# schema_v4_2.net
KiCad netlist of a schematic drawn in EAGLE
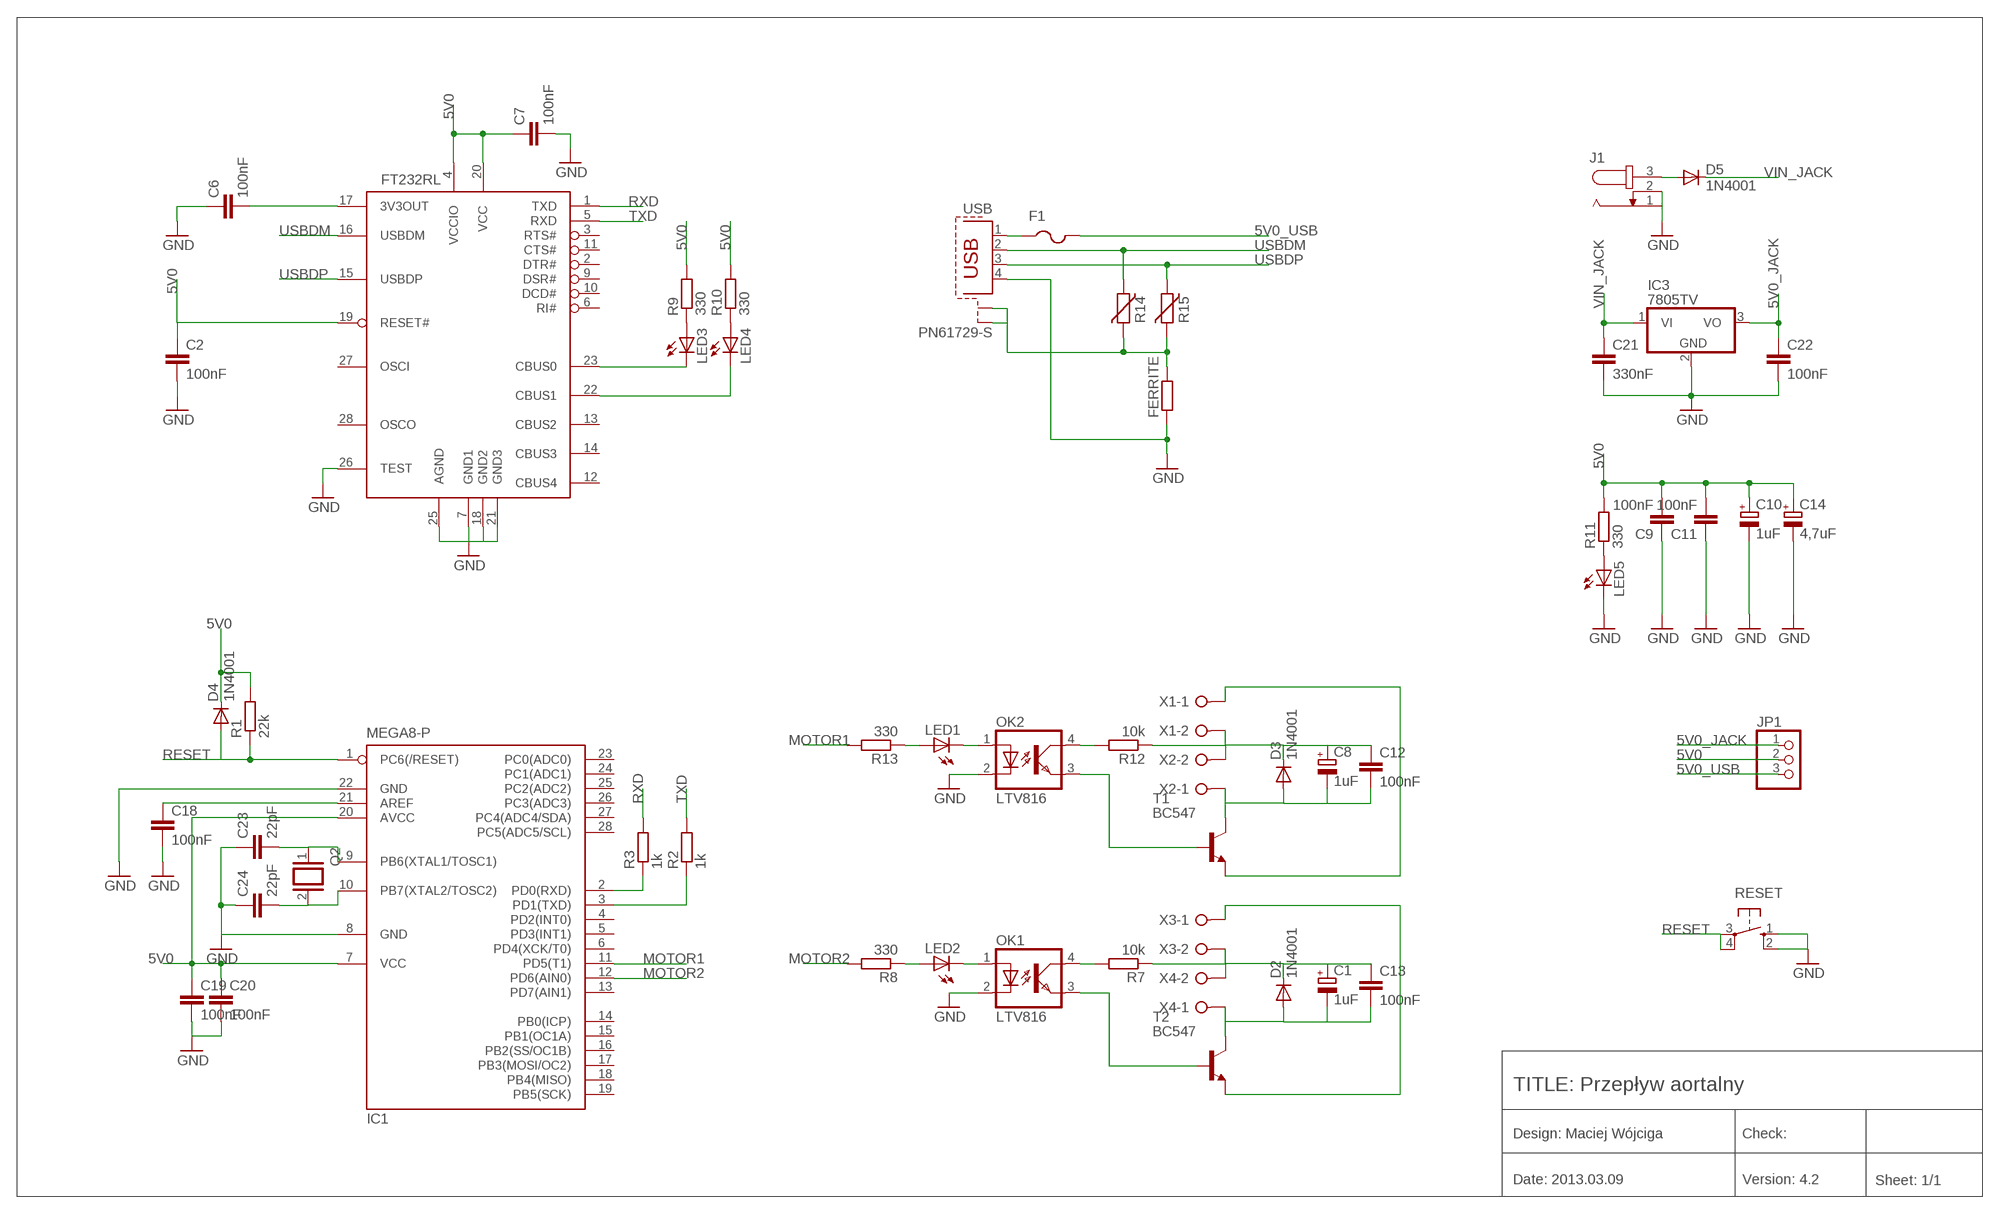
[diagram p0: schematic, sheet 1]

(export (version "E")
  (design (tool "Eeschema 10.0.6"))
  (components
    (comp (ref "C1")
      (value "1uF")
      (footprint "eagle-import:E2,5-5")
      (libsource (lib "eagle-import") (part "CPOL-EUE2.5-5"))
    )
    (comp (ref "C2")
      (value "100nF")
      (footprint "eagle-import:C0603K")
      (libsource (lib "eagle-import") (part "C-EUC0603K"))
    )
    (comp (ref "C6")
      (value "100nF")
      (footprint "eagle-import:C0603K")
      (libsource (lib "eagle-import") (part "C-EUC0603K"))
    )
    (comp (ref "C7")
      (value "100nF")
      (footprint "eagle-import:C0603K")
      (libsource (lib "eagle-import") (part "C-EUC0603K"))
    )
    (comp (ref "C8")
      (value "1uF")
      (footprint "eagle-import:E2,5-5")
      (libsource (lib "eagle-import") (part "CPOL-EUE2.5-5"))
    )
    (comp (ref "C9")
      (value "100nF")
      (footprint "eagle-import:C025-025X050")
      (libsource (lib "eagle-import") (part "C-EU025-025X050"))
    )
    (comp (ref "C10")
      (value "1uF")
      (footprint "eagle-import:E2,5-5")
      (libsource (lib "eagle-import") (part "CPOL-EUE2.5-5"))
    )
    (comp (ref "C11")
      (value "100nF")
      (footprint "eagle-import:C025-025X050")
      (libsource (lib "eagle-import") (part "C-EU025-025X050"))
    )
    (comp (ref "C12")
      (value "100nF")
      (footprint "eagle-import:C025-025X050")
      (libsource (lib "eagle-import") (part "C-EU025-025X050"))
    )
    (comp (ref "C13")
      (value "100nF")
      (footprint "eagle-import:C025-025X050")
      (libsource (lib "eagle-import") (part "C-EU025-025X050"))
    )
    (comp (ref "C14")
      (value "4,7uF")
      (footprint "eagle-import:E2,5-5")
      (libsource (lib "eagle-import") (part "CPOL-EUE2.5-5"))
    )
    (comp (ref "C18")
      (value "100nF")
      (footprint "eagle-import:C0805")
      (libsource (lib "eagle-import") (part "C-EUC0805"))
    )
    (comp (ref "C19")
      (value "100nF")
      (footprint "eagle-import:C025-025X050")
      (libsource (lib "eagle-import") (part "C-EU025-025X050"))
    )
    (comp (ref "C20")
      (value "100nF")
      (footprint "eagle-import:C025-025X050")
      (libsource (lib "eagle-import") (part "C-EU025-025X050"))
    )
    (comp (ref "C21")
      (value "330nF")
      (footprint "eagle-import:C025-025X050")
      (libsource (lib "eagle-import") (part "C-EU025-025X050"))
    )
    (comp (ref "C22")
      (value "100nF")
      (footprint "eagle-import:C025-025X050")
      (libsource (lib "eagle-import") (part "C-EU025-025X050"))
    )
    (comp (ref "C23")
      (value "22pF")
      (footprint "eagle-import:C025-025X050")
      (libsource (lib "eagle-import") (part "C-EU025-025X050"))
    )
    (comp (ref "C24")
      (value "22pF")
      (footprint "eagle-import:C025-025X050")
      (libsource (lib "eagle-import") (part "C-EU025-025X050"))
    )
    (comp (ref "D2")
      (value "1N4001")
      (footprint "eagle-import:DO41-10")
      (libsource (lib "eagle-import") (part "1N4004"))
    )
    (comp (ref "D3")
      (value "1N4001")
      (footprint "eagle-import:DO41-10")
      (libsource (lib "eagle-import") (part "1N4004"))
    )
    (comp (ref "D4")
      (value "1N4001")
      (footprint "eagle-import:DO41-10")
      (libsource (lib "eagle-import") (part "1N4004"))
    )
    (comp (ref "D5")
      (value "1N4001")
      (footprint "eagle-import:DO41-10")
      (libsource (lib "eagle-import") (part "1N4004"))
    )
    (comp (ref "F1")
      (value "PTCFUSE-1812")
      (footprint "eagle-import:1812")
      (libsource (lib "eagle-import") (part "PTCFUSE-1812"))
    )
    (comp (ref "FERRITE")
      (value "R-EU_M0805")
      (footprint "eagle-import:M0805")
      (libsource (lib "eagle-import") (part "resistor_R-EU_M0805"))
    )
    (comp (ref "FT232RL")
      (value "FT232RL")
      (footprint "eagle-import:SSOP28DB")
      (libsource (lib "eagle-import") (part "FT232RL"))
    )
    (comp (ref "IC1")
      (value "MEGA8-P")
      (footprint "eagle-import:DIL28-3")
      (libsource (lib "eagle-import") (part "MEGA8-P"))
    )
    (comp (ref "IC3")
      (value "7805TV")
      (footprint "eagle-import:TO220V")
      (libsource (lib "eagle-import") (part "78TV05"))
    )
    (comp (ref "J1")
      (value "JACK-PLUG0")
      (footprint "eagle-import:SPC4077")
      (libsource (lib "eagle-import") (part "JACK-PLUG0"))
    )
    (comp (ref "JP1")
      (value "PINHD-1X3")
      (footprint "eagle-import:1X03")
      (libsource (lib "eagle-import") (part "PINHD-1X3"))
    )
    (comp (ref "LED1")
      (value "LED3MM")
      (footprint "eagle-import:LED3MM")
      (libsource (lib "eagle-import") (part "LED3MM"))
    )
    (comp (ref "LED2")
      (value "LED3MM")
      (footprint "eagle-import:LED3MM")
      (libsource (lib "eagle-import") (part "LED3MM"))
    )
    (comp (ref "LED3")
      (value "LED3MM")
      (footprint "eagle-import:LED3MM")
      (libsource (lib "eagle-import") (part "LED3MM"))
    )
    (comp (ref "LED4")
      (value "LED3MM")
      (footprint "eagle-import:LED3MM")
      (libsource (lib "eagle-import") (part "LED3MM"))
    )
    (comp (ref "LED5")
      (value "LED3MM")
      (footprint "eagle-import:LED3MM")
      (libsource (lib "eagle-import") (part "LED3MM"))
    )
    (comp (ref "OK1")
      (value "LTV816")
      (footprint "eagle-import:DIL04")
      (libsource (lib "eagle-import") (part "LTV816"))
    )
    (comp (ref "OK2")
      (value "LTV816")
      (footprint "eagle-import:DIL04")
      (libsource (lib "eagle-import") (part "LTV816"))
    )
    (comp (ref "Q2")
      (value "XTAL/S")
      (footprint "eagle-import:QS")
      (libsource (lib "eagle-import") (part "XTAL/S"))
    )
    (comp (ref "R1")
      (value "22k")
      (footprint "eagle-import:0207_10")
      (libsource (lib "eagle-import") (part "R-EU_0207/10"))
    )
    (comp (ref "R2")
      (value "1k")
      (footprint "eagle-import:0207_10")
      (libsource (lib "eagle-import") (part "R-EU_0207/10"))
    )
    (comp (ref "R3")
      (value "1k")
      (footprint "eagle-import:0207_10")
      (libsource (lib "eagle-import") (part "R-EU_0207/10"))
    )
    (comp (ref "R7")
      (value "10k")
      (footprint "eagle-import:0207_10")
      (libsource (lib "eagle-import") (part "R-EU_0207/10"))
    )
    (comp (ref "R8")
      (value "330")
      (footprint "eagle-import:0207_10")
      (libsource (lib "eagle-import") (part "R-EU_0207/10"))
    )
    (comp (ref "R9")
      (value "330")
      (footprint "eagle-import:0207_10")
      (libsource (lib "eagle-import") (part "R-EU_0207/10"))
    )
    (comp (ref "R10")
      (value "330")
      (footprint "eagle-import:0207_10")
      (libsource (lib "eagle-import") (part "R-EU_0207/10"))
    )
    (comp (ref "R11")
      (value "330")
      (footprint "eagle-import:0207_10")
      (libsource (lib "eagle-import") (part "R-EU_0207/10"))
    )
    (comp (ref "R12")
      (value "10k")
      (footprint "eagle-import:0207_10")
      (libsource (lib "eagle-import") (part "R-EU_0207/10"))
    )
    (comp (ref "R13")
      (value "330")
      (footprint "eagle-import:0207_10")
      (libsource (lib "eagle-import") (part "R-EU_0207/10"))
    )
    (comp (ref "R14")
      (value "VARISTORCN0603")
      (footprint "eagle-import:CT_CN0603")
      (libsource (lib "eagle-import") (part "VARISTORCN0603"))
    )
    (comp (ref "R15")
      (value "VARISTORCN0603")
      (footprint "eagle-import:CT_CN0603")
      (libsource (lib "eagle-import") (part "VARISTORCN0603"))
    )
    (comp (ref "RESET")
      (value "10-XX")
      (footprint "eagle-import:B3F-10XX")
      (fields (field (name "MPN") "B3F-1000"))
      (libsource (lib "eagle-import") (part "10-XX"))
    )
    (comp (ref "T1")
      (value "BC547")
      (footprint "eagle-import:TO92")
      (libsource (lib "eagle-import") (part "BC547"))
    )
    (comp (ref "T2")
      (value "BC547")
      (footprint "eagle-import:TO92")
      (libsource (lib "eagle-import") (part "BC547"))
    )
    (comp (ref "USB")
      (value "PN61729-S")
      (footprint "eagle-import:PN61729-S")
      (fields (field (name "OC_FARNELL") "unknown") (field (name "OC_NEWARK") "unknown"))
      (libsource (lib "eagle-import") (part "PN61729-S"))
    )
    (comp (ref "X1")
      (value "W237-02P")
      (footprint "eagle-import:W237-132")
      (fields (field (name "OC_FARNELL") "unknown") (field (name "OC_NEWARK") "unknown"))
      (libsource (lib "eagle-import") (part "W237-02P"))
    )
    (comp (ref "X2")
      (value "W237-02P")
      (footprint "eagle-import:W237-132")
      (fields (field (name "OC_FARNELL") "unknown") (field (name "OC_NEWARK") "unknown"))
      (libsource (lib "eagle-import") (part "W237-02P"))
    )
    (comp (ref "X3")
      (value "W237-02P")
      (footprint "eagle-import:W237-132")
      (fields (field (name "OC_FARNELL") "unknown") (field (name "OC_NEWARK") "unknown"))
      (libsource (lib "eagle-import") (part "W237-02P"))
    )
    (comp (ref "X4")
      (value "W237-02P")
      (footprint "eagle-import:W237-132")
      (fields (field (name "OC_FARNELL") "unknown") (field (name "OC_NEWARK") "unknown"))
      (libsource (lib "eagle-import") (part "W237-02P"))
    )
  )
  (nets
    (net (code "1") (name "/5V0") (class "Default")
      (node (ref "C10") (pin "+") (pinfunction "+_+") (pintype "passive"))
      (node (ref "C11") (pin "2") (pinfunction "2_2") (pintype "passive"))
      (node (ref "C14") (pin "+") (pinfunction "+_+") (pintype "passive"))
      (node (ref "C19") (pin "1") (pinfunction "1_1") (pintype "passive"))
      (node (ref "C2") (pin "1") (pinfunction "1_1") (pintype "passive"))
      (node (ref "C20") (pin "1") (pinfunction "1_1") (pintype "passive"))
      (node (ref "C7") (pin "1") (pinfunction "1_1") (pintype "passive"))
      (node (ref "C9") (pin "2") (pinfunction "2_2") (pintype "passive"))
      (node (ref "D4") (pin "C") (pinfunction "C_C") (pintype "passive"))
      (node (ref "FT232RL") (pin "19") (pinfunction "RESET#_19") (pintype "input"))
      (node (ref "FT232RL") (pin "20") (pinfunction "VCC_20") (pintype "power_in"))
      (node (ref "FT232RL") (pin "4") (pinfunction "VCCIO_4") (pintype "power_in"))
      (node (ref "IC1") (pin "20") (pinfunction "AVCC_20") (pintype "power_in"))
      (node (ref "IC1") (pin "7") (pinfunction "VCC_7") (pintype "power_in"))
      (node (ref "JP1") (pin "2") (pinfunction "2_2") (pintype "passive"))
      (node (ref "R1") (pin "2") (pinfunction "2_2") (pintype "passive"))
      (node (ref "R10") (pin "2") (pinfunction "2_2") (pintype "passive"))
      (node (ref "R11") (pin "2") (pinfunction "2_2") (pintype "passive"))
      (node (ref "R9") (pin "2") (pinfunction "2_2") (pintype "passive"))
    )
    (net (code "2") (name "/5V0_JACK") (class "Default")
      (node (ref "C22") (pin "1") (pinfunction "1_1") (pintype "passive"))
      (node (ref "IC3") (pin "3") (pinfunction "VO_3") (pintype "passive"))
      (node (ref "JP1") (pin "1") (pinfunction "1_1") (pintype "passive"))
    )
    (net (code "3") (name "/5V0_USB") (class "Default")
      (node (ref "F1") (pin "2") (pinfunction "2_2") (pintype "passive"))
      (node (ref "JP1") (pin "3") (pinfunction "3_3") (pintype "passive"))
    )
    (net (code "4") (name "/MOTOR1") (class "Default")
      (node (ref "IC1") (pin "11") (pinfunction "PD5(T1)_11") (pintype "bidirectional"))
      (node (ref "R13") (pin "2") (pinfunction "2_2") (pintype "passive"))
    )
    (net (code "5") (name "/MOTOR2") (class "Default")
      (node (ref "IC1") (pin "12") (pinfunction "PD6(AIN0)_12") (pintype "bidirectional"))
      (node (ref "R8") (pin "2") (pinfunction "2_2") (pintype "passive"))
    )
    (net (code "6") (name "/RESET") (class "Default")
      (node (ref "D4") (pin "A") (pinfunction "A_A") (pintype "passive"))
      (node (ref "IC1") (pin "1") (pinfunction "PC6(/RESET)_1") (pintype "bidirectional"))
      (node (ref "R1") (pin "1") (pinfunction "1_1") (pintype "passive"))
      (node (ref "RESET") (pin "3") (pinfunction "P_3") (pintype "passive"))
      (node (ref "RESET") (pin "4") (pinfunction "P1_4") (pintype "passive"))
    )
    (net (code "7") (name "/RXD") (class "Default")
      (node (ref "FT232RL") (pin "1") (pinfunction "TXD_1") (pintype "output"))
      (node (ref "R3") (pin "2") (pinfunction "2_2") (pintype "passive"))
    )
    (net (code "8") (name "/TXD") (class "Default")
      (node (ref "FT232RL") (pin "5") (pinfunction "RXD_5") (pintype "input"))
      (node (ref "R2") (pin "2") (pinfunction "2_2") (pintype "passive"))
    )
    (net (code "9") (name "/USBDM") (class "Default")
      (node (ref "FT232RL") (pin "16") (pinfunction "USBDM_16") (pintype "bidirectional"))
      (node (ref "R14") (pin "1") (pinfunction "1_1") (pintype "passive"))
      (node (ref "USB") (pin "2") (pinfunction "2_2") (pintype "passive"))
    )
    (net (code "10") (name "/USBDP") (class "Default")
      (node (ref "FT232RL") (pin "15") (pinfunction "USBDP_15") (pintype "bidirectional"))
      (node (ref "R15") (pin "1") (pinfunction "1_1") (pintype "passive"))
      (node (ref "USB") (pin "3") (pinfunction "3_3") (pintype "passive"))
    )
    (net (code "11") (name "/VIN_JACK") (class "Default")
      (node (ref "C21") (pin "1") (pinfunction "1_1") (pintype "passive"))
      (node (ref "D5") (pin "C") (pinfunction "C_C") (pintype "passive"))
      (node (ref "IC3") (pin "1") (pinfunction "VI_1") (pintype "input"))
    )
    (net (code "12") (name "GND") (class "Default")
      (node (ref "C10") (pin "-") (pinfunction "-_-") (pintype "passive"))
      (node (ref "C11") (pin "1") (pinfunction "1_1") (pintype "passive"))
      (node (ref "C14") (pin "-") (pinfunction "-_-") (pintype "passive"))
      (node (ref "C18") (pin "2") (pinfunction "2_2") (pintype "passive"))
      (node (ref "C19") (pin "2") (pinfunction "2_2") (pintype "passive"))
      (node (ref "C2") (pin "2") (pinfunction "2_2") (pintype "passive"))
      (node (ref "C20") (pin "2") (pinfunction "2_2") (pintype "passive"))
      (node (ref "C21") (pin "2") (pinfunction "2_2") (pintype "passive"))
      (node (ref "C22") (pin "2") (pinfunction "2_2") (pintype "passive"))
      (node (ref "C23") (pin "1") (pinfunction "1_1") (pintype "passive"))
      (node (ref "C24") (pin "1") (pinfunction "1_1") (pintype "passive"))
      (node (ref "C6") (pin "1") (pinfunction "1_1") (pintype "passive"))
      (node (ref "C7") (pin "2") (pinfunction "2_2") (pintype "passive"))
      (node (ref "C9") (pin "1") (pinfunction "1_1") (pintype "passive"))
      (node (ref "FERRITE") (pin "1") (pinfunction "1_1") (pintype "passive"))
      (node (ref "FT232RL") (pin "18") (pinfunction "GND2_18") (pintype "power_in"))
      (node (ref "FT232RL") (pin "21") (pinfunction "GND3_21") (pintype "power_in"))
      (node (ref "FT232RL") (pin "25") (pinfunction "AGND_25") (pintype "power_in"))
      (node (ref "FT232RL") (pin "26") (pinfunction "TEST_26") (pintype "input"))
      (node (ref "FT232RL") (pin "7") (pinfunction "GND1_7") (pintype "power_in"))
      (node (ref "IC1") (pin "22") (pinfunction "GND_22") (pintype "power_in"))
      (node (ref "IC1") (pin "8") (pinfunction "GND_8") (pintype "power_in"))
      (node (ref "IC3") (pin "2") (pinfunction "GND_2") (pintype "passive"))
      (node (ref "J1") (pin "1") (pinfunction "1_1") (pintype "passive"))
      (node (ref "J1") (pin "2") (pinfunction "2_2") (pintype "passive"))
      (node (ref "LED5") (pin "K") (pinfunction "C_K") (pintype "passive"))
      (node (ref "OK1") (pin "2") (pinfunction "C_2") (pintype "passive"))
      (node (ref "OK2") (pin "2") (pinfunction "C_2") (pintype "passive"))
      (node (ref "RESET") (pin "1") (pinfunction "S_1") (pintype "passive"))
      (node (ref "RESET") (pin "2") (pinfunction "S1_2") (pintype "passive"))
      (node (ref "USB") (pin "4") (pinfunction "4_4") (pintype "passive"))
    )
    (net (code "13") (name "Net-(D5-PadA)") (class "Default")
      (node (ref "D5") (pin "A") (pinfunction "A_A") (pintype "passive"))
      (node (ref "J1") (pin "3") (pinfunction "3_3") (pintype "passive"))
    )
    (net (code "14") (name "Net-(F1-Pad1)") (class "Default")
      (node (ref "F1") (pin "1") (pinfunction "1_1") (pintype "passive"))
      (node (ref "USB") (pin "1") (pinfunction "1_1") (pintype "passive"))
    )
    (net (code "15") (name "Net-(FERRITE-Pad2)") (class "Default")
      (node (ref "FERRITE") (pin "2") (pinfunction "2_2") (pintype "passive"))
      (node (ref "R14") (pin "2") (pinfunction "2_2") (pintype "passive"))
      (node (ref "R15") (pin "2") (pinfunction "2_2") (pintype "passive"))
      (node (ref "USB") (pin "S1") (pinfunction "S1_S1") (pintype "passive"))
      (node (ref "USB") (pin "S2") (pinfunction "S2_S2") (pintype "passive"))
    )
    (net (code "16") (name "Net-(FT232RL-3V3OUT)") (class "Default")
      (node (ref "C6") (pin "2") (pinfunction "2_2") (pintype "passive"))
      (node (ref "FT232RL") (pin "17") (pinfunction "3V3OUT_17") (pintype "output"))
    )
    (net (code "17") (name "Net-(FT232RL-CBUS0)") (class "Default")
      (node (ref "FT232RL") (pin "23") (pinfunction "CBUS0_23") (pintype "bidirectional"))
      (node (ref "LED3") (pin "K") (pinfunction "C_K") (pintype "passive"))
    )
    (net (code "18") (name "Net-(FT232RL-CBUS1)") (class "Default")
      (node (ref "FT232RL") (pin "22") (pinfunction "CBUS1_22") (pintype "bidirectional"))
      (node (ref "LED4") (pin "K") (pinfunction "C_K") (pintype "passive"))
    )
    (net (code "19") (name "Net-(IC1-AREF)") (class "Default")
      (node (ref "C18") (pin "1") (pinfunction "1_1") (pintype "passive"))
      (node (ref "IC1") (pin "21") (pinfunction "AREF_21") (pintype "passive"))
    )
    (net (code "20") (name "Net-(IC1-PB6(XTAL1{slash}TOSC1))") (class "Default")
      (node (ref "C23") (pin "2") (pinfunction "2_2") (pintype "passive"))
      (node (ref "IC1") (pin "9") (pinfunction "PB6(XTAL1/TOSC1)_9") (pintype "bidirectional"))
      (node (ref "Q2") (pin "1") (pinfunction "1_1") (pintype "passive"))
    )
    (net (code "21") (name "Net-(IC1-PB7(XTAL2{slash}TOSC2))") (class "Default")
      (node (ref "C24") (pin "2") (pinfunction "2_2") (pintype "passive"))
      (node (ref "IC1") (pin "10") (pinfunction "PB7(XTAL2/TOSC2)_10") (pintype "bidirectional"))
      (node (ref "Q2") (pin "2") (pinfunction "2_2") (pintype "passive"))
    )
    (net (code "22") (name "Net-(IC1-PD0(RXD))") (class "Default")
      (node (ref "IC1") (pin "2") (pinfunction "PD0(RXD)_2") (pintype "bidirectional"))
      (node (ref "R3") (pin "1") (pinfunction "1_1") (pintype "passive"))
    )
    (net (code "23") (name "Net-(IC1-PD1(TXD))") (class "Default")
      (node (ref "IC1") (pin "3") (pinfunction "PD1(TXD)_3") (pintype "bidirectional"))
      (node (ref "R2") (pin "1") (pinfunction "1_1") (pintype "passive"))
    )
    (net (code "24") (name "Net-(LED1-C)") (class "Default")
      (node (ref "LED1") (pin "K") (pinfunction "C_K") (pintype "passive"))
      (node (ref "OK2") (pin "1") (pinfunction "A_1") (pintype "passive"))
    )
    (net (code "25") (name "Net-(LED1-PadA)") (class "Default")
      (node (ref "LED1") (pin "A") (pinfunction "A_A") (pintype "passive"))
      (node (ref "R13") (pin "1") (pinfunction "1_1") (pintype "passive"))
    )
    (net (code "26") (name "Net-(LED2-C)") (class "Default")
      (node (ref "LED2") (pin "K") (pinfunction "C_K") (pintype "passive"))
      (node (ref "OK1") (pin "1") (pinfunction "A_1") (pintype "passive"))
    )
    (net (code "27") (name "Net-(LED2-PadA)") (class "Default")
      (node (ref "LED2") (pin "A") (pinfunction "A_A") (pintype "passive"))
      (node (ref "R8") (pin "1") (pinfunction "1_1") (pintype "passive"))
    )
    (net (code "28") (name "Net-(LED3-PadA)") (class "Default")
      (node (ref "LED3") (pin "A") (pinfunction "A_A") (pintype "passive"))
      (node (ref "R9") (pin "1") (pinfunction "1_1") (pintype "passive"))
    )
    (net (code "29") (name "Net-(LED4-PadA)") (class "Default")
      (node (ref "LED4") (pin "A") (pinfunction "A_A") (pintype "passive"))
      (node (ref "R10") (pin "1") (pinfunction "1_1") (pintype "passive"))
    )
    (net (code "30") (name "Net-(LED5-PadA)") (class "Default")
      (node (ref "LED5") (pin "A") (pinfunction "A_A") (pintype "passive"))
      (node (ref "R11") (pin "1") (pinfunction "1_1") (pintype "passive"))
    )
    (net (code "31") (name "Net-(OK1-COL)") (class "Default")
      (node (ref "OK1") (pin "4") (pinfunction "COL_4") (pintype "passive"))
      (node (ref "R7") (pin "2") (pinfunction "2_2") (pintype "passive"))
    )
    (net (code "32") (name "Net-(OK1-EMIT)") (class "Default")
      (node (ref "OK1") (pin "3") (pinfunction "EMIT_3") (pintype "passive"))
      (node (ref "T2") (pin "2") (pinfunction "B_2") (pintype "passive"))
    )
    (net (code "33") (name "Net-(OK2-COL)") (class "Default")
      (node (ref "OK2") (pin "4") (pinfunction "COL_4") (pintype "passive"))
      (node (ref "R12") (pin "2") (pinfunction "2_2") (pintype "passive"))
    )
    (net (code "34") (name "Net-(OK2-EMIT)") (class "Default")
      (node (ref "OK2") (pin "3") (pinfunction "EMIT_3") (pintype "passive"))
      (node (ref "T1") (pin "2") (pinfunction "B_2") (pintype "passive"))
    )
    (net (code "35") (name "Net-(T1-C)") (class "Default")
      (node (ref "C12") (pin "2") (pinfunction "2_2") (pintype "passive"))
      (node (ref "C8") (pin "-") (pinfunction "-_-") (pintype "passive"))
      (node (ref "D3") (pin "A") (pinfunction "A_A") (pintype "passive"))
      (node (ref "T1") (pin "3") (pinfunction "C_3") (pintype "passive"))
      (node (ref "X2") (pin "1") (pinfunction "KL_1") (pintype "passive"))
    )
    (net (code "36") (name "Net-(T1-E)") (class "Default")
      (node (ref "T1") (pin "1") (pinfunction "E_1") (pintype "passive"))
      (node (ref "X1") (pin "1") (pinfunction "KL_1") (pintype "passive"))
    )
    (net (code "37") (name "Net-(T2-C)") (class "Default")
      (node (ref "C1") (pin "-") (pinfunction "-_-") (pintype "passive"))
      (node (ref "C13") (pin "2") (pinfunction "2_2") (pintype "passive"))
      (node (ref "D2") (pin "A") (pinfunction "A_A") (pintype "passive"))
      (node (ref "T2") (pin "3") (pinfunction "C_3") (pintype "passive"))
      (node (ref "X4") (pin "1") (pinfunction "KL_1") (pintype "passive"))
    )
    (net (code "38") (name "Net-(T2-E)") (class "Default")
      (node (ref "T2") (pin "1") (pinfunction "E_1") (pintype "passive"))
      (node (ref "X3") (pin "1") (pinfunction "KL_1") (pintype "passive"))
    )
    (net (code "39") (name "Net-(X1B-KL)") (class "Default")
      (node (ref "C12") (pin "1") (pinfunction "1_1") (pintype "passive"))
      (node (ref "C8") (pin "+") (pinfunction "+_+") (pintype "passive"))
      (node (ref "D3") (pin "C") (pinfunction "C_C") (pintype "passive"))
      (node (ref "R12") (pin "1") (pinfunction "1_1") (pintype "passive"))
      (node (ref "X1") (pin "2") (pinfunction "KL_2") (pintype "passive"))
      (node (ref "X2") (pin "2") (pinfunction "KL_2") (pintype "passive"))
    )
    (net (code "40") (name "Net-(X3B-KL)") (class "Default")
      (node (ref "C1") (pin "+") (pinfunction "+_+") (pintype "passive"))
      (node (ref "C13") (pin "1") (pinfunction "1_1") (pintype "passive"))
      (node (ref "D2") (pin "C") (pinfunction "C_C") (pintype "passive"))
      (node (ref "R7") (pin "1") (pinfunction "1_1") (pintype "passive"))
      (node (ref "X3") (pin "2") (pinfunction "KL_2") (pintype "passive"))
      (node (ref "X4") (pin "2") (pinfunction "KL_2") (pintype "passive"))
    )
    (net (code "41") (name "unconnected-(FT232RL-CBUS2-Pad13)") (class "Default")
      (node (ref "FT232RL") (pin "13") (pinfunction "CBUS2_13") (pintype "bidirectional"))
    )
    (net (code "42") (name "unconnected-(FT232RL-CBUS3-Pad14)") (class "Default")
      (node (ref "FT232RL") (pin "14") (pinfunction "CBUS3_14") (pintype "bidirectional"))
    )
    (net (code "43") (name "unconnected-(FT232RL-CBUS4-Pad12)") (class "Default")
      (node (ref "FT232RL") (pin "12") (pinfunction "CBUS4_12") (pintype "bidirectional"))
    )
    (net (code "44") (name "unconnected-(FT232RL-CTS#-Pad11)") (class "Default")
      (node (ref "FT232RL") (pin "11") (pinfunction "CTS#_11") (pintype "input"))
    )
    (net (code "45") (name "unconnected-(FT232RL-DCD#-Pad10)") (class "Default")
      (node (ref "FT232RL") (pin "10") (pinfunction "DCD#_10") (pintype "input"))
    )
    (net (code "46") (name "unconnected-(FT232RL-DSR#-Pad9)") (class "Default")
      (node (ref "FT232RL") (pin "9") (pinfunction "DSR#_9") (pintype "input"))
    )
    (net (code "47") (name "unconnected-(FT232RL-DTR#-Pad2)") (class "Default")
      (node (ref "FT232RL") (pin "2") (pinfunction "DTR#_2") (pintype "output"))
    )
    (net (code "48") (name "unconnected-(FT232RL-OSCI-Pad27)") (class "Default")
      (node (ref "FT232RL") (pin "27") (pinfunction "OSCI_27") (pintype "input"))
    )
    (net (code "49") (name "unconnected-(FT232RL-OSCO-Pad28)") (class "Default")
      (node (ref "FT232RL") (pin "28") (pinfunction "OSCO_28") (pintype "output"))
    )
    (net (code "50") (name "unconnected-(FT232RL-RI#-Pad6)") (class "Default")
      (node (ref "FT232RL") (pin "6") (pinfunction "RI#_6") (pintype "input"))
    )
    (net (code "51") (name "unconnected-(FT232RL-RTS#-Pad3)") (class "Default")
      (node (ref "FT232RL") (pin "3") (pinfunction "RTS#_3") (pintype "output"))
    )
    (net (code "52") (name "unconnected-(IC1-PB0(ICP)-Pad14)") (class "Default")
      (node (ref "IC1") (pin "14") (pinfunction "PB0(ICP)_14") (pintype "bidirectional"))
    )
    (net (code "53") (name "unconnected-(IC1-PB1(OC1A)-Pad15)") (class "Default")
      (node (ref "IC1") (pin "15") (pinfunction "PB1(OC1A)_15") (pintype "bidirectional"))
    )
    (net (code "54") (name "unconnected-(IC1-PB2(SS{slash}OC1B)-Pad16)") (class "Default")
      (node (ref "IC1") (pin "16") (pinfunction "PB2(SS/OC1B)_16") (pintype "bidirectional"))
    )
    (net (code "55") (name "unconnected-(IC1-PB3(MOSI{slash}OC2)-Pad17)") (class "Default")
      (node (ref "IC1") (pin "17") (pinfunction "PB3(MOSI/OC2)_17") (pintype "bidirectional"))
    )
    (net (code "56") (name "unconnected-(IC1-PB4(MISO)-Pad18)") (class "Default")
      (node (ref "IC1") (pin "18") (pinfunction "PB4(MISO)_18") (pintype "bidirectional"))
    )
    (net (code "57") (name "unconnected-(IC1-PB5(SCK)-Pad19)") (class "Default")
      (node (ref "IC1") (pin "19") (pinfunction "PB5(SCK)_19") (pintype "bidirectional"))
    )
    (net (code "58") (name "unconnected-(IC1-PC0(ADC0)-Pad23)") (class "Default")
      (node (ref "IC1") (pin "23") (pinfunction "PC0(ADC0)_23") (pintype "bidirectional"))
    )
    (net (code "59") (name "unconnected-(IC1-PC1(ADC1)-Pad24)") (class "Default")
      (node (ref "IC1") (pin "24") (pinfunction "PC1(ADC1)_24") (pintype "bidirectional"))
    )
    (net (code "60") (name "unconnected-(IC1-PC2(ADC2)-Pad25)") (class "Default")
      (node (ref "IC1") (pin "25") (pinfunction "PC2(ADC2)_25") (pintype "bidirectional"))
    )
    (net (code "61") (name "unconnected-(IC1-PC3(ADC3)-Pad26)") (class "Default")
      (node (ref "IC1") (pin "26") (pinfunction "PC3(ADC3)_26") (pintype "bidirectional"))
    )
    (net (code "62") (name "unconnected-(IC1-PC4(ADC4{slash}SDA)-Pad27)") (class "Default")
      (node (ref "IC1") (pin "27") (pinfunction "PC4(ADC4/SDA)_27") (pintype "bidirectional"))
    )
    (net (code "63") (name "unconnected-(IC1-PC5(ADC5{slash}SCL)-Pad28)") (class "Default")
      (node (ref "IC1") (pin "28") (pinfunction "PC5(ADC5/SCL)_28") (pintype "bidirectional"))
    )
    (net (code "64") (name "unconnected-(IC1-PD2(INT0)-Pad4)") (class "Default")
      (node (ref "IC1") (pin "4") (pinfunction "PD2(INT0)_4") (pintype "bidirectional"))
    )
    (net (code "65") (name "unconnected-(IC1-PD3(INT1)-Pad5)") (class "Default")
      (node (ref "IC1") (pin "5") (pinfunction "PD3(INT1)_5") (pintype "bidirectional"))
    )
    (net (code "66") (name "unconnected-(IC1-PD4(XCK{slash}T0)-Pad6)") (class "Default")
      (node (ref "IC1") (pin "6") (pinfunction "PD4(XCK/T0)_6") (pintype "bidirectional"))
    )
    (net (code "67") (name "unconnected-(IC1-PD7(AIN1)-Pad13)") (class "Default")
      (node (ref "IC1") (pin "13") (pinfunction "PD7(AIN1)_13") (pintype "bidirectional"))
    )
  )
)
